# LM2596_HV.net
KiCad netlist of a schematic drawn in Altium Designer
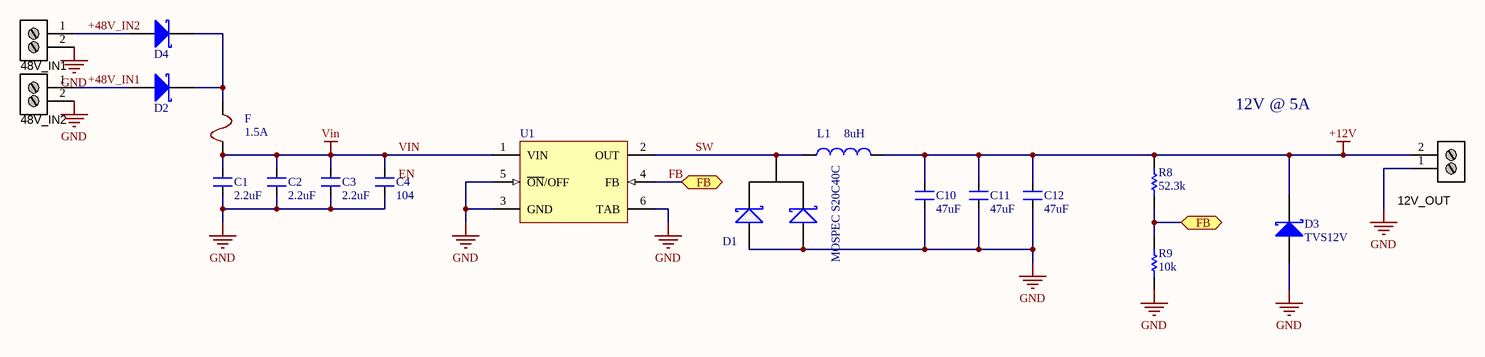
[diagram p0: LM2596_HV.SchDoc]

(export (version "E")
  (design (tool "Eeschema 10.0.6"))
  (components
    (comp (ref "12V_OUT")
      (value "Stackable ScrewTerm")
      (footprint "2P_PCB_ScrewTerm_200mil")
      (description "Terminal Block Screw Type THT 2-Position 3.81mm pitch")
      (libsource (lib "PBL - Connectors") (part "2P_ScrewTerm_90S_3.81MM"))
    )
    (comp (ref "48V_IN1")
      (value "Stackable ScrewTerm")
      (footprint "2P_PCB_ScrewTerm_200mil")
      (description "Terminal Block Screw Type THT 2-Position 3.81mm pitch")
      (libsource (lib "") (part "2P_ScrewTerm_90S_3.81MM_1"))
    )
    (comp (ref "48V_IN2")
      (value "Stackable ScrewTerm")
      (footprint "2P_PCB_ScrewTerm_200mil")
      (description "Terminal Block Screw Type THT 2-Position 3.81mm pitch")
      (libsource (lib "") (part "2P_ScrewTerm_90S_3.81MM_1"))
    )
    (comp (ref "C1")
      (value "2.2uF")
      (footprint "CAPC3225N")
      (fields (field (name "Comment") "CAP NP"))
      (libsource (lib "Tuan") (part "CAP NP"))
    )
    (comp (ref "C2")
      (value "2.2uF")
      (footprint "CAPC3225N")
      (fields (field (name "Comment") "CAP NP"))
      (libsource (lib "Tuan") (part "CAP NP"))
    )
    (comp (ref "C3")
      (value "2.2uF")
      (footprint "CAPC3225N")
      (fields (field (name "Comment") "CAP NP"))
      (libsource (lib "Tuan") (part "CAP NP"))
    )
    (comp (ref "C4")
      (value "104")
      (footprint "CAPC1608N")
      (fields (field (name "Comment") "CAP NP"))
      (libsource (lib "Tuan") (part "CAP NP"))
    )
    (comp (ref "C10")
      (value "47uF")
      (footprint "CAPC3225N")
      (fields (field (name "Comment") "CAP NP"))
      (libsource (lib "Tuan") (part "CAP NP"))
    )
    (comp (ref "C11")
      (value "47uF")
      (footprint "CAPC3225N")
      (fields (field (name "Comment") "CAP NP"))
      (libsource (lib "Tuan") (part "CAP NP"))
    )
    (comp (ref "C12")
      (value "47uF")
      (footprint "CAPC3225N")
      (fields (field (name "Comment") "CAP NP"))
      (libsource (lib "Tuan") (part "CAP NP"))
    )
    (comp (ref "D1") (value "MOSPEC S20C40C") (footprint "TO-220") (libsource (lib "Tuan") (part "Diode x2")))
    (comp (ref "D2") (value "~") (footprint "DO-214AC") (libsource (lib "Tuan") (part "Diode Schottky")))
    (comp (ref "D3") (value "TVS12V") (footprint "DO-214AA") (libsource (lib "Tuan") (part "Diode Schottky")))
    (comp (ref "D4") (value "SS14") (footprint "DO-214AC") (libsource (lib "Tuan") (part "Diode Schottky")))
    (comp (ref "F") (value "1.5A") (footprint "FUSE_SR-5-BK") (libsource (lib "Tuan") (part "Fuse")))
    (comp (ref "L1")
      (value "8uH")
      (footprint "Toroid")
      (fields (field (name "Comment") "Inductor"))
      (libsource (lib "Tuan") (part "Inductor"))
    )
    (comp (ref "R8")
      (value "52.3k")
      (footprint "RESC2012N")
      (fields (field (name "Comment") "Res"))
      (libsource (lib "Tuan") (part "Res"))
    )
    (comp (ref "R9")
      (value "10k")
      (footprint "RESC2012N")
      (fields (field (name "Comment") "Res"))
      (libsource (lib "Tuan") (part "Res"))
    )
    (comp (ref "U1")
      (value "LM2596S-ADJ")
      (footprint "TS5B_N")
      (description "SIMPLE SWITCHER Power Converter 150 KHz 3A Step-Down Voltage Regulator")
      (fields
        (field (name "MANUFACTURER") "National Semiconductor")
        (field (name "DIGIKEYPARTNUMBER") "LM2596S-ADJ-ND")
        (field (name "PUBLISHER") "Altium Limited")
      )
      (libsource (lib "NSC Switcher") (part "LM2596S-ADJ"))
    )
  )
  (nets
    (net (code "1") (name "+12V") (class "Default")
      (node (ref "12V_OUT") (pin "2") (pinfunction "2_2") (pintype "passive"))
      (node (ref "C10") (pin "2") (pinfunction "2_2") (pintype "passive"))
      (node (ref "C11") (pin "2") (pinfunction "2_2") (pintype "passive"))
      (node (ref "C12") (pin "2") (pinfunction "2_2") (pintype "passive"))
      (node (ref "D3") (pin "2") (pinfunction "K_2") (pintype "passive"))
      (node (ref "L1") (pin "2") (pinfunction "2_2") (pintype "passive"))
      (node (ref "R8") (pin "2") (pinfunction "2_2") (pintype "passive"))
    )
    (net (code "2") (name "/+48V_IN1") (class "Default")
      (node (ref "48V_IN2") (pin "1") (pinfunction "1_1") (pintype "passive"))
      (node (ref "D2") (pin "1") (pinfunction "A_1") (pintype "passive"))
    )
    (net (code "3") (name "/+48V_IN2") (class "Default")
      (node (ref "48V_IN1") (pin "1") (pinfunction "1_1") (pintype "passive"))
      (node (ref "D4") (pin "1") (pinfunction "A_1") (pintype "passive"))
    )
    (net (code "5") (name "/FB") (class "Default")
      (node (ref "R8") (pin "1") (pinfunction "1_1") (pintype "passive"))
      (node (ref "R9") (pin "2") (pinfunction "2_2") (pintype "passive"))
      (node (ref "U1") (pin "4") (pinfunction "FB_4") (pintype "input"))
    )
    (net (code "6") (name "/SW") (class "Default")
      (node (ref "D1") (pin "2") (pinfunction "A2_2") (pintype "passive"))
      (node (ref "L1") (pin "1") (pinfunction "1_1") (pintype "passive"))
      (node (ref "U1") (pin "2") (pinfunction "OUT_2") (pintype "power_in"))
    )
    (net (code "7") (name "GND") (class "Default")
      (node (ref "12V_OUT") (pin "1") (pinfunction "1_1") (pintype "passive"))
      (node (ref "48V_IN1") (pin "2") (pinfunction "2_2") (pintype "passive"))
      (node (ref "48V_IN2") (pin "2") (pinfunction "2_2") (pintype "passive"))
      (node (ref "C1") (pin "1") (pinfunction "1_1") (pintype "passive"))
      (node (ref "C10") (pin "1") (pinfunction "1_1") (pintype "passive"))
      (node (ref "C11") (pin "1") (pinfunction "1_1") (pintype "passive"))
      (node (ref "C12") (pin "1") (pinfunction "1_1") (pintype "passive"))
      (node (ref "C2") (pin "1") (pinfunction "1_1") (pintype "passive"))
      (node (ref "C3") (pin "1") (pinfunction "1_1") (pintype "passive"))
      (node (ref "C4") (pin "1") (pinfunction "1_1") (pintype "passive"))
      (node (ref "D1") (pin "1") (pinfunction "A1_1") (pintype "passive"))
      (node (ref "D1") (pin "3") (pinfunction "K_3") (pintype "passive"))
      (node (ref "D3") (pin "1") (pinfunction "A_1") (pintype "passive"))
      (node (ref "R9") (pin "1") (pinfunction "1_1") (pintype "passive"))
      (node (ref "U1") (pin "3") (pinfunction "GND_3") (pintype "power_in"))
      (node (ref "U1") (pin "5") (pinfunction "~{ON}/OFF_5") (pintype "input"))
      (node (ref "U1") (pin "6") (pinfunction "TAB_6") (pintype "power_in"))
    )
    (net (code "8") (name "Net-(D2-K)") (class "Default")
      (node (ref "D2") (pin "2") (pinfunction "K_2") (pintype "passive"))
      (node (ref "D4") (pin "2") (pinfunction "K_2") (pintype "passive"))
      (node (ref "F") (pin "2") (pinfunction "2_2") (pintype "passive"))
    )
    (net (code "9") (name "Vin") (class "Default")
      (node (ref "C1") (pin "2") (pinfunction "2_2") (pintype "passive"))
      (node (ref "C2") (pin "2") (pinfunction "2_2") (pintype "passive"))
      (node (ref "C3") (pin "2") (pinfunction "2_2") (pintype "passive"))
      (node (ref "C4") (pin "2") (pinfunction "2_2") (pintype "passive"))
      (node (ref "F") (pin "1") (pinfunction "1_1") (pintype "passive"))
      (node (ref "U1") (pin "1") (pinfunction "VIN_1") (pintype "power_in"))
    )
  )
)
